# 6_Pole_Butterworth_Bandpass_Filter.net
KiCad netlist of a schematic drawn in Altium Designer
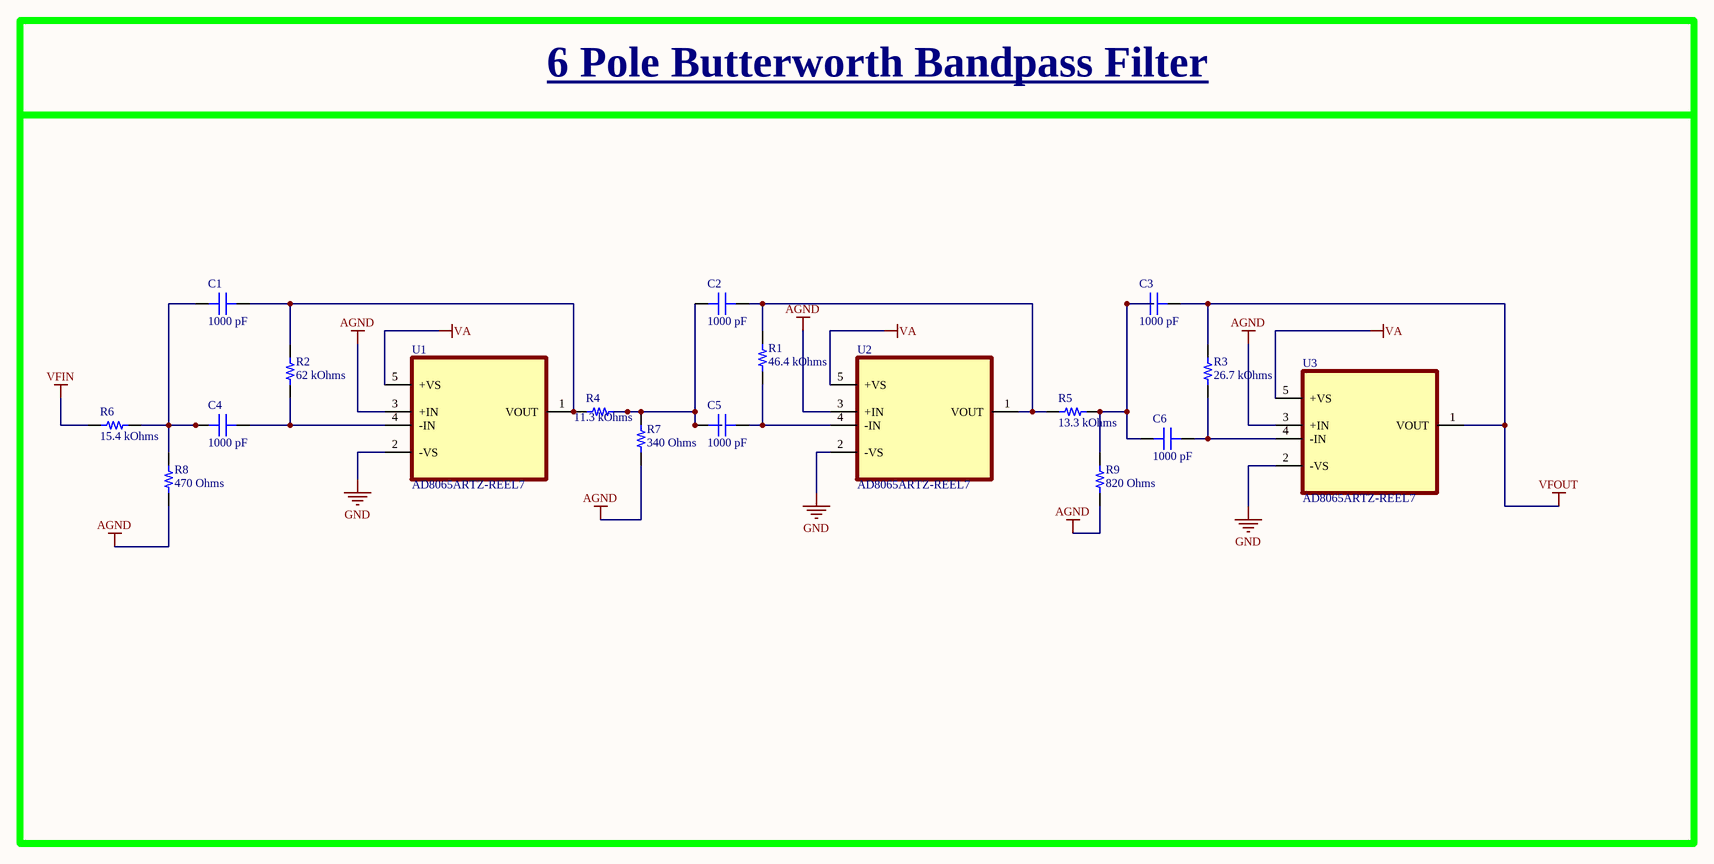
[diagram p0: 6 Pole Butterworth Bandpass Filter.SchDoc]

(export (version "E")
  (design (tool "Eeschema 10.0.6"))
  (components
    (comp (ref "C1")
      (value "1000 pF")
      (footprint "CAP 0805_2012 RF")
      (description "CAP CER 1000PF 500V X7R 0805")
      (fields (field (name "PART NUMBER") "CS0805KRX7RBBB102") (field (name "MANUFACTURER") "Yageo"))
      (libsource (lib "Celestial Altium Library - altium_library") (part "Capacitor"))
    )
    (comp (ref "C2")
      (value "1000 pF")
      (footprint "CAP 0805_2012 RF")
      (description "CAP CER 1000PF 500V X7R 0805")
      (fields (field (name "PART NUMBER") "CS0805KRX7RBBB102") (field (name "MANUFACTURER") "Yageo"))
      (libsource (lib "Celestial Altium Library - altium_library") (part "Capacitor"))
    )
    (comp (ref "C3")
      (value "1000 pF")
      (footprint "CAP 0805_2012 RF")
      (description "CAP CER 1000PF 500V X7R 0805")
      (fields (field (name "PART NUMBER") "CS0805KRX7RBBB102") (field (name "MANUFACTURER") "Yageo"))
      (libsource (lib "Celestial Altium Library - altium_library") (part "Capacitor"))
    )
    (comp (ref "C4")
      (value "1000 pF")
      (footprint "CAP 0805_2012 RF")
      (description "CAP CER 1000PF 500V X7R 0805")
      (fields (field (name "PART NUMBER") "CS0805KRX7RBBB102") (field (name "MANUFACTURER") "Yageo"))
      (libsource (lib "Celestial Altium Library - altium_library") (part "Capacitor"))
    )
    (comp (ref "C5")
      (value "1000 pF")
      (footprint "CAP 0805_2012 RF")
      (description "CAP CER 1000PF 500V X7R 0805")
      (fields (field (name "PART NUMBER") "CS0805KRX7RBBB102") (field (name "MANUFACTURER") "Yageo"))
      (libsource (lib "Celestial Altium Library - altium_library") (part "Capacitor"))
    )
    (comp (ref "C6")
      (value "1000 pF")
      (footprint "CAP 0805_2012 RF")
      (description "CAP CER 1000PF 500V X7R 0805")
      (fields (field (name "PART NUMBER") "CS0805KRX7RBBB102") (field (name "MANUFACTURER") "Yageo"))
      (libsource (lib "Celestial Altium Library - altium_library") (part "Capacitor"))
    )
    (comp (ref "R1")
      (value "46.4 kOhms")
      (footprint "RES 1206_3216 RF")
      (description "RES SMD 46.4K OHM 0.5% 1/8W 0805")
      (fields (field (name "PART NUMBER") "RT0805DRE0746K4L") (field (name "MANUFACTURER") "Yageo"))
      (libsource (lib "Celestial Altium Library - altium_library") (part "Resistor"))
    )
    (comp (ref "R2")
      (value "62 kOhms")
      (footprint "RES 1206_3216 RF")
      (description "RES SMD 62K OHM 0.1% 1/10W 0805")
      (fields
        (field (name "PART NUMBER") "CPF0805B62KE1")
        (field (name "MANUFACTURER") "TE Connectivity Passive Product")
      )
      (libsource (lib "Celestial Altium Library - altium_library") (part "Resistor"))
    )
    (comp (ref "R3")
      (value "26.7 kOhms")
      (footprint "RES 1206_3216 RF")
      (description "RES SMD 26.7K OHM 1% 1/8W 0805")
      (fields
        (field (name "PART NUMBER") "ERJ-6ENF2672V")
        (field (name "MANUFACTURER") "Panasonic Electronic Components")
      )
      (libsource (lib "Celestial Altium Library - altium_library") (part "Resistor"))
    )
    (comp (ref "R4")
      (value "11.3 kOhms")
      (footprint "RES 1206_3216 RF")
      (description "RES 11.3K OHM 1% 1/4W 0805")
      (fields
        (field (name "PART NUMBER") "RK73H2ATTD1132F")
        (field (name "MANUFACTURER") "KOA Speer Electronics, Inc.")
      )
      (libsource (lib "Celestial Altium Library - altium_library") (part "Resistor"))
    )
    (comp (ref "R5")
      (value "13.3 kOhms")
      (footprint "RES 1206_3216 RF")
      (description "RES 13.3K OHM 1% 1/4W 1206")
      (fields
        (field (name "PART NUMBER") "RK73H2BTTD1332F")
        (field (name "MANUFACTURER") "KOA Speer Electronics, Inc.")
      )
      (libsource (lib "Celestial Altium Library - altium_library") (part "Resistor"))
    )
    (comp (ref "R6")
      (value "15.4 kOhms")
      (footprint "RES 1206_3216 RF")
      (description "RES SMD 15.4K OHM 1% 1/8W 0805")
      (fields
        (field (name "PART NUMBER") "ERJ-6ENF1542V")
        (field (name "MANUFACTURER") "Panasonic Electronic Components")
      )
      (libsource (lib "Celestial Altium Library - altium_library") (part "Resistor"))
    )
    (comp (ref "R7")
      (value "340 Ohms")
      (footprint "RES 1206_3216 RF")
      (description "RES SMD 340 OHM 1% 1/4W 1206")
      (fields
        (field (name "PART NUMBER") "ERJ-8ENF3400V")
        (field (name "MANUFACTURER") "Panasonic Electronic Components")
      )
      (libsource (lib "Celestial Altium Library - altium_library") (part "Resistor"))
    )
    (comp (ref "R8")
      (value "470 Ohms")
      (footprint "RES 1206_3216 RF")
      (description "RES 470 OHM 1% 1/3W 0805")
      (fields
        (field (name "PART NUMBER") "CRGP0805F470R")
        (field (name "MANUFACTURER") "TE Connectivity Passive Product")
      )
      (libsource (lib "Celestial Altium Library - altium_library") (part "Resistor"))
    )
    (comp (ref "R9")
      (value "820 Ohms")
      (footprint "RES 1206_3216 RF")
      (description "RES 0805 820R 5% 125MW TC200 LOW")
      (fields (field (name "PART NUMBER") "CR0805-JW-821EPF") (field (name "MANUFACTURER") "Bourns Inc."))
      (libsource (lib "Celestial Altium Library - altium_library") (part "Resistor"))
    )
    (comp (ref "U1")
      (value "AD8065ARTZ-REEL7")
      (footprint "SOT95P290X145-5N")
      (description "Voltage Feedback Amplifier 1 Circuit Rail-to-Rail SOT-23-5")
      (fields (field (name "MF") "Analog Devices"))
      (libsource (lib "AD8065ARTZ-REEL7") (part "AD8065ARTZ-REEL7"))
    )
    (comp (ref "U2")
      (value "AD8065ARTZ-REEL7")
      (footprint "SOT95P290X145-5N")
      (description "Voltage Feedback Amplifier 1 Circuit Rail-to-Rail SOT-23-5")
      (fields (field (name "MF") "Analog Devices"))
      (libsource (lib "AD8065ARTZ-REEL7") (part "AD8065ARTZ-REEL7"))
    )
    (comp (ref "U3")
      (value "AD8065ARTZ-REEL7")
      (footprint "SOT95P290X145-5N")
      (description "Voltage Feedback Amplifier 1 Circuit Rail-to-Rail SOT-23-5")
      (fields (field (name "MF") "Analog Devices"))
      (libsource (lib "AD8065ARTZ-REEL7") (part "AD8065ARTZ-REEL7"))
    )
  )
  (nets
    (net (code "1") (name "AGND") (class "Default")
      (node (ref "R7") (pin "1") (pinfunction "1_1") (pintype "passive"))
      (node (ref "R8") (pin "1") (pinfunction "1_1") (pintype "passive"))
      (node (ref "R9") (pin "1") (pinfunction "1_1") (pintype "passive"))
      (node (ref "U1") (pin "3") (pinfunction "+IN_3") (pintype "passive"))
      (node (ref "U2") (pin "3") (pinfunction "+IN_3") (pintype "passive"))
      (node (ref "U3") (pin "3") (pinfunction "+IN_3") (pintype "passive"))
    )
    (net (code "2") (name "GND") (class "Default")
      (node (ref "U1") (pin "2") (pinfunction "-VS_2") (pintype "power_in"))
      (node (ref "U2") (pin "2") (pinfunction "-VS_2") (pintype "power_in"))
      (node (ref "U3") (pin "2") (pinfunction "-VS_2") (pintype "power_in"))
    )
    (net (code "3") (name "Net-(C1-Pad1)") (class "Default")
      (node (ref "C1") (pin "1") (pinfunction "1_1") (pintype "passive"))
      (node (ref "C4") (pin "1") (pinfunction "1_1") (pintype "passive"))
      (node (ref "R6") (pin "2") (pinfunction "2_2") (pintype "passive"))
      (node (ref "R8") (pin "2") (pinfunction "2_2") (pintype "passive"))
    )
    (net (code "4") (name "Net-(C2-Pad1)") (class "Default")
      (node (ref "C2") (pin "1") (pinfunction "1_1") (pintype "passive"))
      (node (ref "C5") (pin "1") (pinfunction "1_1") (pintype "passive"))
      (node (ref "R4") (pin "2") (pinfunction "2_2") (pintype "passive"))
      (node (ref "R7") (pin "2") (pinfunction "2_2") (pintype "passive"))
    )
    (net (code "5") (name "Net-(C3-Pad1)") (class "Default")
      (node (ref "C3") (pin "1") (pinfunction "1_1") (pintype "passive"))
      (node (ref "C6") (pin "1") (pinfunction "1_1") (pintype "passive"))
      (node (ref "R5") (pin "2") (pinfunction "2_2") (pintype "passive"))
      (node (ref "R9") (pin "2") (pinfunction "2_2") (pintype "passive"))
    )
    (net (code "6") (name "Net-(U1--IN)") (class "Default")
      (node (ref "C4") (pin "2") (pinfunction "2_2") (pintype "passive"))
      (node (ref "R2") (pin "1") (pinfunction "1_1") (pintype "passive"))
      (node (ref "U1") (pin "4") (pinfunction "-IN_4") (pintype "passive"))
    )
    (net (code "7") (name "Net-(U1-VOUT)") (class "Default")
      (node (ref "C1") (pin "2") (pinfunction "2_2") (pintype "passive"))
      (node (ref "R2") (pin "2") (pinfunction "2_2") (pintype "passive"))
      (node (ref "R4") (pin "1") (pinfunction "1_1") (pintype "passive"))
      (node (ref "U1") (pin "1") (pinfunction "VOUT_1") (pintype "passive"))
    )
    (net (code "8") (name "Net-(U2--IN)") (class "Default")
      (node (ref "C5") (pin "2") (pinfunction "2_2") (pintype "passive"))
      (node (ref "R1") (pin "1") (pinfunction "1_1") (pintype "passive"))
      (node (ref "U2") (pin "4") (pinfunction "-IN_4") (pintype "passive"))
    )
    (net (code "9") (name "Net-(U2-VOUT)") (class "Default")
      (node (ref "C2") (pin "2") (pinfunction "2_2") (pintype "passive"))
      (node (ref "R1") (pin "2") (pinfunction "2_2") (pintype "passive"))
      (node (ref "R5") (pin "1") (pinfunction "1_1") (pintype "passive"))
      (node (ref "U2") (pin "1") (pinfunction "VOUT_1") (pintype "passive"))
    )
    (net (code "10") (name "Net-(U3--IN)") (class "Default")
      (node (ref "C6") (pin "2") (pinfunction "2_2") (pintype "passive"))
      (node (ref "R3") (pin "1") (pinfunction "1_1") (pintype "passive"))
      (node (ref "U3") (pin "4") (pinfunction "-IN_4") (pintype "passive"))
    )
    (net (code "11") (name "VA") (class "Default")
      (node (ref "U1") (pin "5") (pinfunction "+VS_5") (pintype "power_in"))
      (node (ref "U2") (pin "5") (pinfunction "+VS_5") (pintype "power_in"))
      (node (ref "U3") (pin "5") (pinfunction "+VS_5") (pintype "power_in"))
    )
    (net (code "12") (name "VFIN") (class "Default")
      (node (ref "R6") (pin "1") (pinfunction "1_1") (pintype "passive"))
    )
    (net (code "13") (name "VFOUT") (class "Default")
      (node (ref "C3") (pin "2") (pinfunction "2_2") (pintype "passive"))
      (node (ref "R3") (pin "2") (pinfunction "2_2") (pintype "passive"))
      (node (ref "U3") (pin "1") (pinfunction "VOUT_1") (pintype "passive"))
    )
  )
)
